# ui_codec.net
KiCad netlist of a schematic drawn in Altium Designer
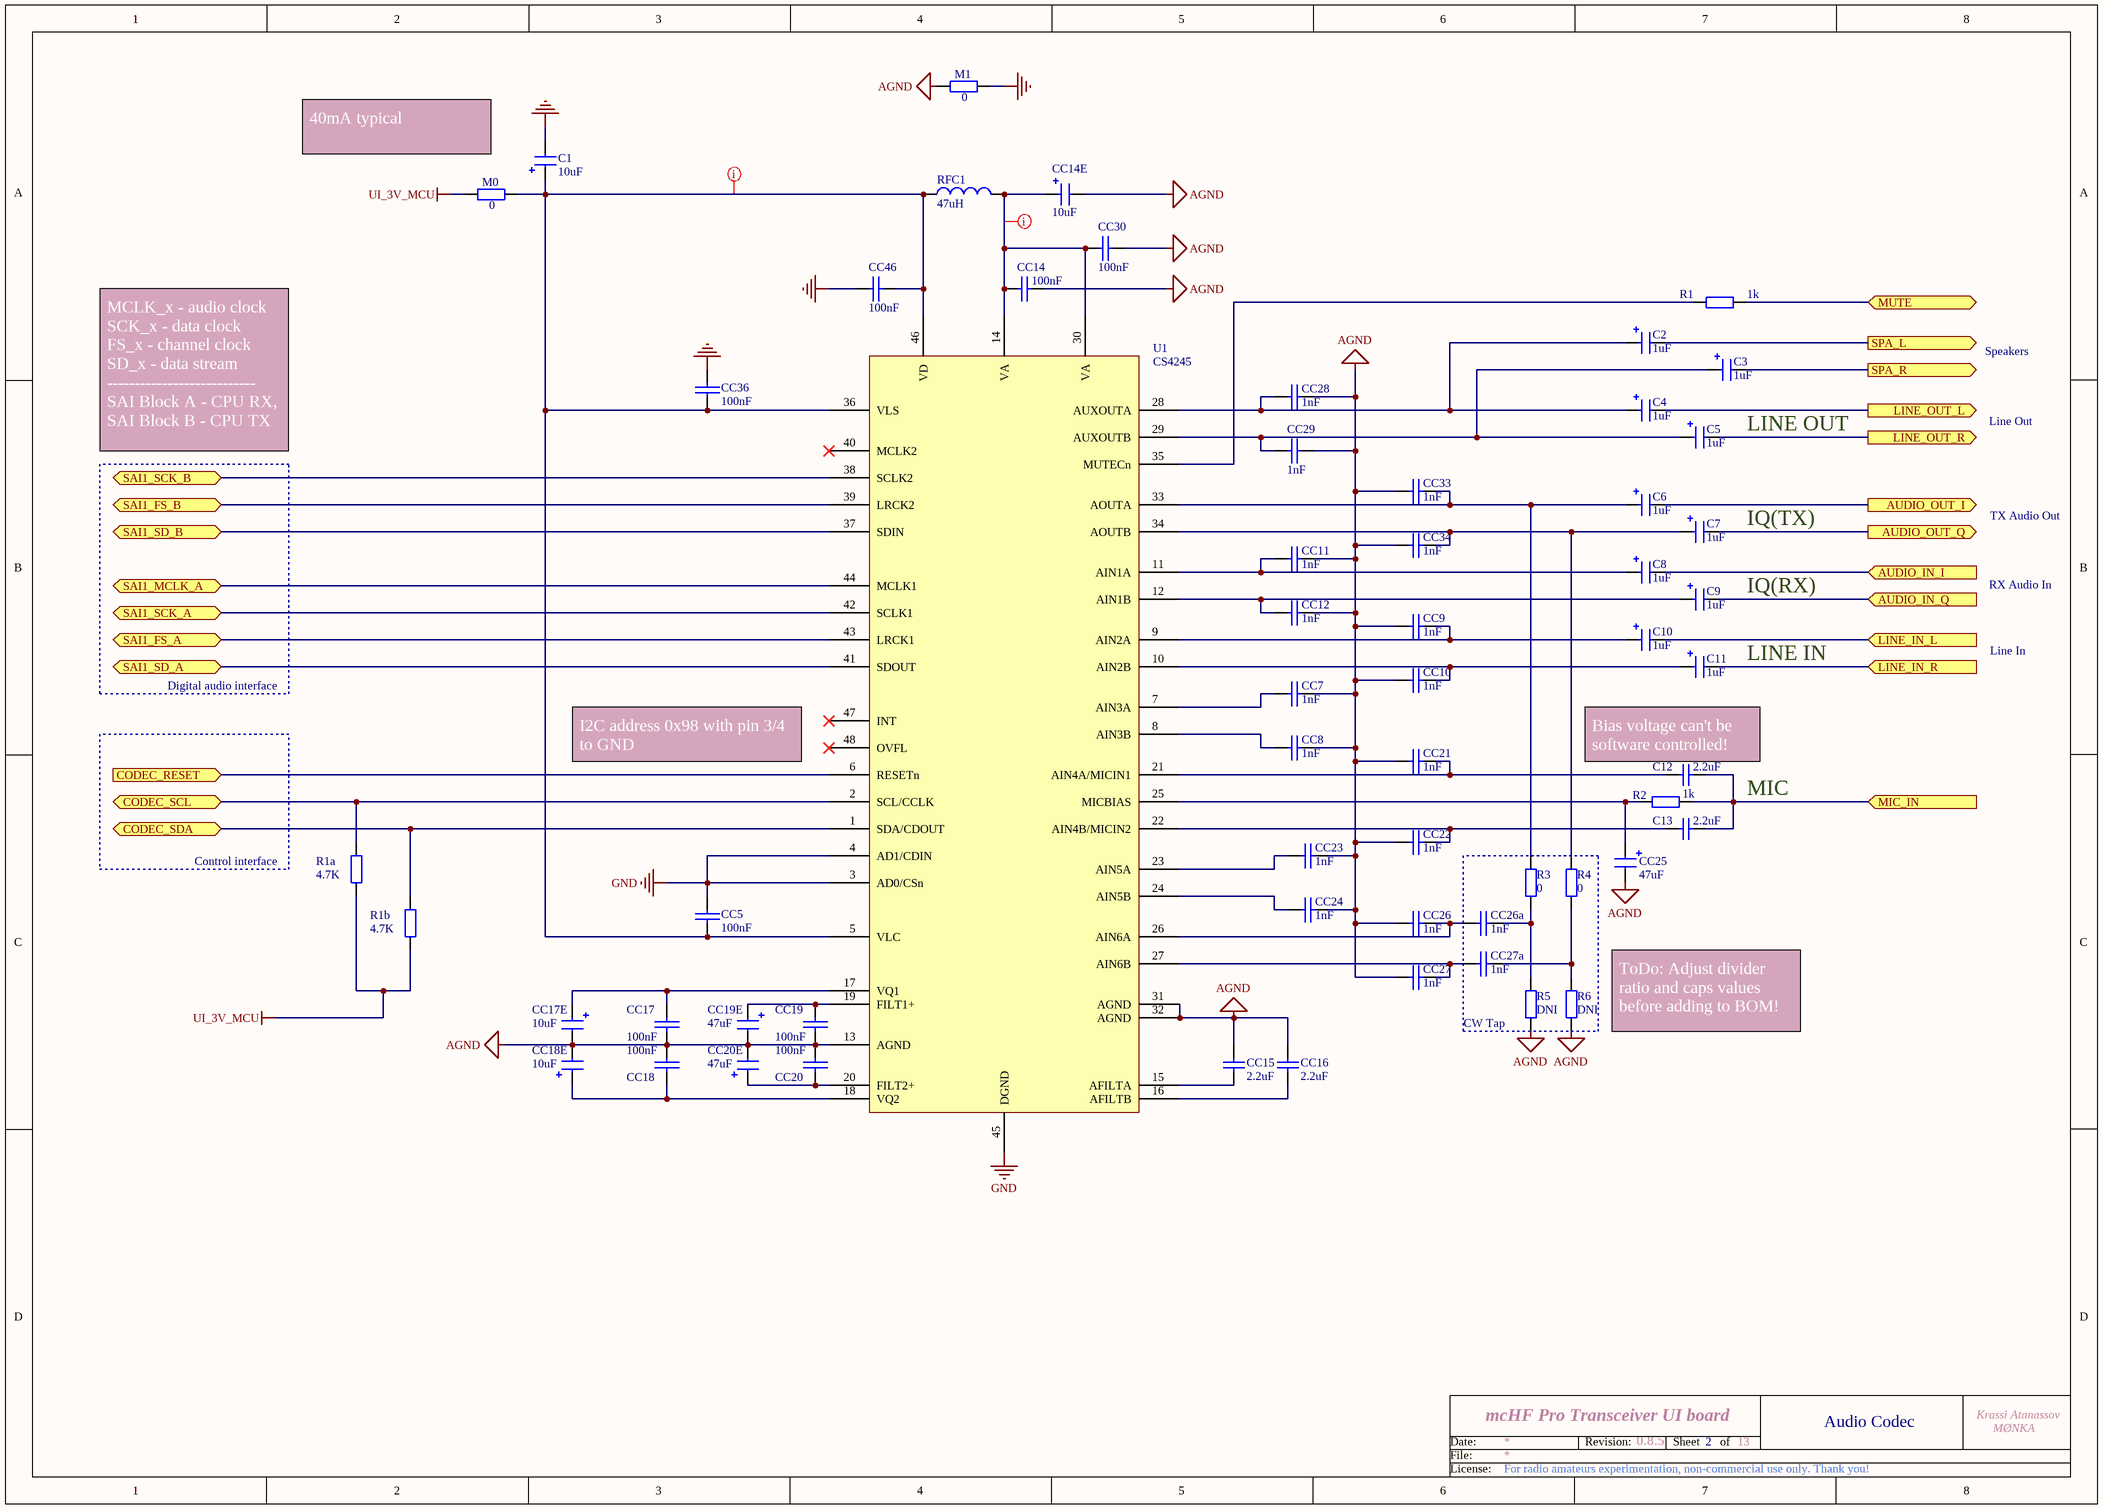
[diagram p0: ui_codec.SchDoc]

(export (version "E")
  (design (tool "Eeschema 10.0.6"))
  (components
    (comp (ref "C1")
      (value "10uF")
      (footprint "1206_Elec_Cap")
      (description "Electrolitic capacitor")
      (libsource (lib "mcHF_ui") (part "CAP-POL"))
    )
    (comp (ref "C2")
      (value "1uF")
      (footprint "1206_Elec_Cap")
      (description "Electrolitic capacitor")
      (libsource (lib "mcHF_ui") (part "CAP-POL"))
    )
    (comp (ref "C3")
      (value "1uF")
      (footprint "1206_Elec_Cap")
      (description "Electrolitic capacitor")
      (libsource (lib "mcHF_ui") (part "CAP-POL"))
    )
    (comp (ref "C4")
      (value "1uF")
      (footprint "1206_Elec_Cap")
      (description "Electrolitic capacitor")
      (libsource (lib "mcHF_ui") (part "CAP-POL"))
    )
    (comp (ref "C5")
      (value "1uF")
      (footprint "1206_Elec_Cap")
      (description "Electrolitic capacitor")
      (libsource (lib "mcHF_ui") (part "CAP-POL"))
    )
    (comp (ref "C6")
      (value "1uF")
      (footprint "1206_Elec_Cap")
      (description "Electrolitic capacitor")
      (libsource (lib "mcHF_ui") (part "CAP-POL"))
    )
    (comp (ref "C7")
      (value "1uF")
      (footprint "1206_Elec_Cap")
      (description "Electrolitic capacitor")
      (libsource (lib "mcHF_ui") (part "CAP-POL"))
    )
    (comp (ref "C8")
      (value "1uF")
      (footprint "1206_Elec_Cap")
      (description "Electrolitic capacitor")
      (libsource (lib "mcHF_ui") (part "CAP-POL"))
    )
    (comp (ref "C9")
      (value "1uF")
      (footprint "1206_Elec_Cap")
      (description "Electrolitic capacitor")
      (libsource (lib "mcHF_ui") (part "CAP-POL"))
    )
    (comp (ref "C10")
      (value "1uF")
      (footprint "1206_Elec_Cap")
      (description "Electrolitic capacitor")
      (libsource (lib "mcHF_ui") (part "CAP-POL"))
    )
    (comp (ref "C11")
      (value "1uF")
      (footprint "1206_Elec_Cap")
      (description "Electrolitic capacitor")
      (libsource (lib "mcHF_ui") (part "CAP-POL"))
    )
    (comp (ref "C12")
      (value "2.2uF")
      (footprint "0805")
      (description "Capacitor")
      (fields (field (name "PUBLISHER") "Altium Limited"))
      (libsource (lib "Miscellaneous Devices") (part "CAP"))
    )
    (comp (ref "C13")
      (value "2.2uF")
      (footprint "0805")
      (description "Capacitor")
      (fields (field (name "PUBLISHER") "Altium Limited"))
      (libsource (lib "Miscellaneous Devices") (part "CAP"))
    )
    (comp (ref "CC5")
      (value "100nF")
      (footprint "0805")
      (description "Capacitor")
      (libsource (lib "mcHF_ui") (part "CAP"))
    )
    (comp (ref "CC7")
      (value "1nF")
      (footprint "0805")
      (description "Capacitor")
      (libsource (lib "mcHF_ui") (part "CAP"))
    )
    (comp (ref "CC8")
      (value "1nF")
      (footprint "0805")
      (description "Capacitor")
      (libsource (lib "mcHF_ui") (part "CAP"))
    )
    (comp (ref "CC9")
      (value "1nF")
      (footprint "0805")
      (description "Capacitor")
      (libsource (lib "mcHF_ui") (part "CAP"))
    )
    (comp (ref "CC10")
      (value "1nF")
      (footprint "0805")
      (description "Capacitor")
      (libsource (lib "mcHF_ui") (part "CAP"))
    )
    (comp (ref "CC11")
      (value "1nF")
      (footprint "0805")
      (description "Capacitor")
      (libsource (lib "mcHF_ui") (part "CAP"))
    )
    (comp (ref "CC12")
      (value "1nF")
      (footprint "0805")
      (description "Capacitor")
      (libsource (lib "mcHF_ui") (part "CAP"))
    )
    (comp (ref "CC14")
      (value "100nF")
      (footprint "0805")
      (description "Capacitor")
      (libsource (lib "mcHF_ui") (part "CAP"))
    )
    (comp (ref "CC14E")
      (value "10uF")
      (footprint "1206_Elec_Cap")
      (description "Electrolitic capacitor")
      (libsource (lib "mcHF_ui") (part "CAP-POL"))
    )
    (comp (ref "CC15")
      (value "2.2uF")
      (footprint "0805")
      (description "Capacitor")
      (fields (field (name "PUBLISHER") "Altium Limited"))
      (libsource (lib "Miscellaneous Devices") (part "CAP"))
    )
    (comp (ref "CC16")
      (value "2.2uF")
      (footprint "0805")
      (description "Capacitor")
      (fields (field (name "PUBLISHER") "Altium Limited"))
      (libsource (lib "Miscellaneous Devices") (part "CAP"))
    )
    (comp (ref "CC17")
      (value "100nF")
      (footprint "0805")
      (description "Capacitor")
      (libsource (lib "mcHF_ui") (part "CAP"))
    )
    (comp (ref "CC17E")
      (value "10uF")
      (footprint "1206_Elec_Cap")
      (description "Electrolitic capacitor")
      (libsource (lib "mcHF_ui") (part "CAP-POL"))
    )
    (comp (ref "CC18")
      (value "100nF")
      (footprint "0805")
      (description "Capacitor")
      (libsource (lib "mcHF_ui") (part "CAP"))
    )
    (comp (ref "CC18E")
      (value "10uF")
      (footprint "1206_Elec_Cap")
      (description "Electrolitic capacitor")
      (libsource (lib "mcHF_ui") (part "CAP-POL"))
    )
    (comp (ref "CC19")
      (value "100nF")
      (footprint "0805")
      (description "Capacitor")
      (libsource (lib "mcHF_ui") (part "CAP"))
    )
    (comp (ref "CC19E")
      (value "47uF")
      (footprint "1206_Elec_Cap")
      (description "Electrolitic capacitor")
      (libsource (lib "mcHF_ui") (part "CAP-POL"))
    )
    (comp (ref "CC20")
      (value "100nF")
      (footprint "0805")
      (description "Capacitor")
      (libsource (lib "mcHF_ui") (part "CAP"))
    )
    (comp (ref "CC20E")
      (value "47uF")
      (footprint "1206_Elec_Cap")
      (description "Electrolitic capacitor")
      (libsource (lib "mcHF_ui") (part "CAP-POL"))
    )
    (comp (ref "CC21")
      (value "1nF")
      (footprint "0805")
      (description "Capacitor")
      (libsource (lib "mcHF_ui") (part "CAP"))
    )
    (comp (ref "CC22")
      (value "1nF")
      (footprint "0805")
      (description "Capacitor")
      (libsource (lib "mcHF_ui") (part "CAP"))
    )
    (comp (ref "CC23")
      (value "1nF")
      (footprint "0805")
      (description "Capacitor")
      (libsource (lib "mcHF_ui") (part "CAP"))
    )
    (comp (ref "CC24")
      (value "1nF")
      (footprint "0805")
      (description "Capacitor")
      (libsource (lib "mcHF_ui") (part "CAP"))
    )
    (comp (ref "CC25")
      (value "47uF")
      (footprint "1206_Elec_Cap")
      (description "Electrolitic capacitor")
      (libsource (lib "mcHF_ui") (part "CAP-POL"))
    )
    (comp (ref "CC26")
      (value "1nF")
      (footprint "0805")
      (description "Capacitor")
      (libsource (lib "mcHF_ui") (part "CAP"))
    )
    (comp (ref "CC26a")
      (value "1nF")
      (footprint "0805")
      (description "Capacitor")
      (libsource (lib "mcHF_ui") (part "CAP"))
    )
    (comp (ref "CC27")
      (value "1nF")
      (footprint "0805")
      (description "Capacitor")
      (libsource (lib "mcHF_ui") (part "CAP"))
    )
    (comp (ref "CC27a")
      (value "1nF")
      (footprint "0805")
      (description "Capacitor")
      (libsource (lib "mcHF_ui") (part "CAP"))
    )
    (comp (ref "CC28")
      (value "1nF")
      (footprint "0805")
      (description "Capacitor")
      (libsource (lib "mcHF_ui") (part "CAP"))
    )
    (comp (ref "CC29")
      (value "1nF")
      (footprint "0805")
      (description "Capacitor")
      (libsource (lib "mcHF_ui") (part "CAP"))
    )
    (comp (ref "CC30")
      (value "100nF")
      (footprint "0805")
      (description "Capacitor")
      (libsource (lib "mcHF_ui") (part "CAP"))
    )
    (comp (ref "CC33")
      (value "1nF")
      (footprint "0805")
      (description "Capacitor")
      (libsource (lib "mcHF_ui") (part "CAP"))
    )
    (comp (ref "CC34")
      (value "1nF")
      (footprint "0805")
      (description "Capacitor")
      (libsource (lib "mcHF_ui") (part "CAP"))
    )
    (comp (ref "CC36")
      (value "100nF")
      (footprint "0805")
      (description "Capacitor")
      (libsource (lib "mcHF_ui") (part "CAP"))
    )
    (comp (ref "CC46")
      (value "100nF")
      (footprint "0805")
      (description "Capacitor")
      (libsource (lib "mcHF_ui") (part "CAP"))
    )
    (comp (ref "M0")
      (value "0")
      (footprint "0805")
      (description "Resistor")
      (libsource (lib "mcHF_rf") (part "RES"))
    )
    (comp (ref "M1")
      (value "0")
      (footprint "0805")
      (description "Resistor")
      (libsource (lib "mcHF_rf") (part "RES"))
    )
    (comp (ref "R1")
      (value "1k")
      (footprint "0805")
      (description "Resistor")
      (libsource (lib "") (part "RES_1"))
    )
    (comp (ref "R1a")
      (value "4.7K")
      (footprint "0805")
      (description "Resistor")
      (libsource (lib "*") (part "RES"))
    )
    (comp (ref "R1b")
      (value "4.7K")
      (footprint "0805")
      (description "Resistor")
      (libsource (lib "*") (part "RES"))
    )
    (comp (ref "R2")
      (value "1k")
      (footprint "0805")
      (description "Resistor")
      (libsource (lib "") (part "RES_1"))
    )
    (comp (ref "R3")
      (value "0")
      (footprint "0805")
      (description "Resistor")
      (libsource (lib "mcHF_ui") (part "RES"))
    )
    (comp (ref "R4")
      (value "0")
      (footprint "0805")
      (description "Resistor")
      (libsource (lib "mcHF_ui") (part "RES"))
    )
    (comp (ref "R5")
      (value "DNI")
      (footprint "0805")
      (description "Resistor")
      (libsource (lib "mcHF_ui") (part "RES"))
    )
    (comp (ref "R6")
      (value "DNI")
      (footprint "0805")
      (description "Resistor")
      (libsource (lib "mcHF_ui") (part "RES"))
    )
    (comp (ref "RFC1")
      (value "47uH")
      (footprint "0805")
      (description "Inductor")
      (libsource (lib "mcHF_ui") (part "Inductor"))
    )
    (comp (ref "U1")
      (value "CS4245")
      (footprint "QUAD48")
      (description "Audio CODEC")
      (libsource (lib "__ui") (part "CS4245"))
    )
  )
  (nets
    (net (code "1") (name "/AUDIO_IN_I") (class "Default")
      (node (ref "C8") (pin "2") (pinfunction "2_2") (pintype "passive"))
    )
    (net (code "2") (name "/AUDIO_IN_Q") (class "Default")
      (node (ref "C9") (pin "2") (pinfunction "2_2") (pintype "passive"))
    )
    (net (code "3") (name "/AUDIO_OUT_I") (class "Default")
      (node (ref "C6") (pin "2") (pinfunction "2_2") (pintype "passive"))
    )
    (net (code "4") (name "/AUDIO_OUT_Q") (class "Default")
      (node (ref "C7") (pin "2") (pinfunction "2_2") (pintype "passive"))
    )
    (net (code "5") (name "/CODEC_RESET") (class "Default")
      (node (ref "U1") (pin "6") (pinfunction "RESETn_6") (pintype "passive"))
    )
    (net (code "6") (name "/CODEC_SCL") (class "Default")
      (node (ref "R1a") (pin "1") (pinfunction "1_1") (pintype "passive"))
      (node (ref "U1") (pin "2") (pinfunction "SCL/CCLK_2") (pintype "passive"))
    )
    (net (code "7") (name "/CODEC_SDA") (class "Default")
      (node (ref "R1b") (pin "1") (pinfunction "1_1") (pintype "passive"))
      (node (ref "U1") (pin "1") (pinfunction "SDA/CDOUT_1") (pintype "passive"))
    )
    (net (code "8") (name "/LINE_IN_L") (class "Default")
      (node (ref "C10") (pin "2") (pinfunction "2_2") (pintype "passive"))
    )
    (net (code "9") (name "/LINE_IN_R") (class "Default")
      (node (ref "C11") (pin "2") (pinfunction "2_2") (pintype "passive"))
    )
    (net (code "10") (name "/LINE_OUT_L") (class "Default")
      (node (ref "C4") (pin "2") (pinfunction "2_2") (pintype "passive"))
    )
    (net (code "11") (name "/LINE_OUT_R") (class "Default")
      (node (ref "C5") (pin "2") (pinfunction "2_2") (pintype "passive"))
    )
    (net (code "12") (name "/MIC_IN") (class "Default")
      (node (ref "C12") (pin "2") (pinfunction "2_2") (pintype "passive"))
      (node (ref "C13") (pin "2") (pinfunction "2_2") (pintype "passive"))
      (node (ref "R2") (pin "1") (pinfunction "1_1") (pintype "passive"))
    )
    (net (code "13") (name "/MUTE") (class "Default")
      (node (ref "R1") (pin "1") (pinfunction "1_1") (pintype "passive"))
    )
    (net (code "14") (name "/SAI1_FS_A") (class "Default")
      (node (ref "U1") (pin "43") (pinfunction "LRCK1_43") (pintype "passive"))
    )
    (net (code "15") (name "/SAI1_FS_B") (class "Default")
      (node (ref "U1") (pin "39") (pinfunction "LRCK2_39") (pintype "passive"))
    )
    (net (code "16") (name "/SAI1_MCLK_A") (class "Default")
      (node (ref "U1") (pin "44") (pinfunction "MCLK1_44") (pintype "passive"))
    )
    (net (code "17") (name "/SAI1_SCK_A") (class "Default")
      (node (ref "U1") (pin "42") (pinfunction "SCLK1_42") (pintype "passive"))
    )
    (net (code "18") (name "/SAI1_SCK_B") (class "Default")
      (node (ref "U1") (pin "38") (pinfunction "SCLK2_38") (pintype "passive"))
    )
    (net (code "19") (name "/SAI1_SD_A") (class "Default")
      (node (ref "U1") (pin "41") (pinfunction "SDOUT_41") (pintype "passive"))
    )
    (net (code "20") (name "/SAI1_SD_B") (class "Default")
      (node (ref "U1") (pin "37") (pinfunction "SDIN_37") (pintype "passive"))
    )
    (net (code "21") (name "/SPA_L") (class "Default")
      (node (ref "C2") (pin "2") (pinfunction "2_2") (pintype "passive"))
    )
    (net (code "22") (name "/SPA_R") (class "Default")
      (node (ref "C3") (pin "2") (pinfunction "2_2") (pintype "passive"))
    )
    (net (code "23") (name "AGND") (class "Default")
      (node (ref "CC10") (pin "2") (pinfunction "2_2") (pintype "passive"))
      (node (ref "CC11") (pin "1") (pinfunction "1_1") (pintype "passive"))
      (node (ref "CC12") (pin "1") (pinfunction "1_1") (pintype "passive"))
      (node (ref "CC14") (pin "1") (pinfunction "1_1") (pintype "passive"))
      (node (ref "CC14E") (pin "2") (pinfunction "2_2") (pintype "passive"))
      (node (ref "CC15") (pin "1") (pinfunction "1_1") (pintype "passive"))
      (node (ref "CC16") (pin "1") (pinfunction "1_1") (pintype "passive"))
      (node (ref "CC17") (pin "1") (pinfunction "1_1") (pintype "passive"))
      (node (ref "CC17E") (pin "2") (pinfunction "2_2") (pintype "passive"))
      (node (ref "CC18") (pin "2") (pinfunction "2_2") (pintype "passive"))
      (node (ref "CC18E") (pin "2") (pinfunction "2_2") (pintype "passive"))
      (node (ref "CC19") (pin "1") (pinfunction "1_1") (pintype "passive"))
      (node (ref "CC19E") (pin "2") (pinfunction "2_2") (pintype "passive"))
      (node (ref "CC20") (pin "2") (pinfunction "2_2") (pintype "passive"))
      (node (ref "CC20E") (pin "2") (pinfunction "2_2") (pintype "passive"))
      (node (ref "CC21") (pin "2") (pinfunction "2_2") (pintype "passive"))
      (node (ref "CC22") (pin "2") (pinfunction "2_2") (pintype "passive"))
      (node (ref "CC23") (pin "1") (pinfunction "1_1") (pintype "passive"))
      (node (ref "CC24") (pin "1") (pinfunction "1_1") (pintype "passive"))
      (node (ref "CC25") (pin "2") (pinfunction "2_2") (pintype "passive"))
      (node (ref "CC26") (pin "2") (pinfunction "2_2") (pintype "passive"))
      (node (ref "CC27") (pin "2") (pinfunction "2_2") (pintype "passive"))
      (node (ref "CC28") (pin "1") (pinfunction "1_1") (pintype "passive"))
      (node (ref "CC29") (pin "1") (pinfunction "1_1") (pintype "passive"))
      (node (ref "CC30") (pin "1") (pinfunction "1_1") (pintype "passive"))
      (node (ref "CC33") (pin "2") (pinfunction "2_2") (pintype "passive"))
      (node (ref "CC34") (pin "2") (pinfunction "2_2") (pintype "passive"))
      (node (ref "CC7") (pin "1") (pinfunction "1_1") (pintype "passive"))
      (node (ref "CC8") (pin "1") (pinfunction "1_1") (pintype "passive"))
      (node (ref "CC9") (pin "2") (pinfunction "2_2") (pintype "passive"))
      (node (ref "M1") (pin "2") (pinfunction "2_2") (pintype "passive"))
      (node (ref "R5") (pin "2") (pinfunction "2_2") (pintype "passive"))
      (node (ref "R6") (pin "2") (pinfunction "2_2") (pintype "passive"))
      (node (ref "U1") (pin "13") (pinfunction "AGND_13") (pintype "passive"))
      (node (ref "U1") (pin "31") (pinfunction "AGND_31") (pintype "passive"))
      (node (ref "U1") (pin "32") (pinfunction "AGND_32") (pintype "passive"))
    )
    (net (code "24") (name "GND") (class "Default")
      (node (ref "C1") (pin "2") (pinfunction "2_2") (pintype "passive"))
      (node (ref "CC36") (pin "2") (pinfunction "2_2") (pintype "passive"))
      (node (ref "CC46") (pin "2") (pinfunction "2_2") (pintype "passive"))
      (node (ref "CC5") (pin "2") (pinfunction "2_2") (pintype "passive"))
      (node (ref "M1") (pin "1") (pinfunction "1_1") (pintype "passive"))
      (node (ref "U1") (pin "3") (pinfunction "AD0/CSn_3") (pintype "passive"))
      (node (ref "U1") (pin "4") (pinfunction "AD1/CDIN_4") (pintype "passive"))
      (node (ref "U1") (pin "45") (pinfunction "DGND_45") (pintype "passive"))
    )
    (net (code "25") (name "Net-(CC14-Pad2)") (class "Default")
      (node (ref "CC14") (pin "2") (pinfunction "2_2") (pintype "passive"))
      (node (ref "CC14E") (pin "1") (pinfunction "1_1") (pintype "passive"))
      (node (ref "CC30") (pin "2") (pinfunction "2_2") (pintype "passive"))
      (node (ref "RFC1") (pin "2") (pinfunction "2_2") (pintype "passive"))
      (node (ref "U1") (pin "14") (pinfunction "VA_14") (pintype "passive"))
      (node (ref "U1") (pin "30") (pinfunction "VA_30") (pintype "passive"))
    )
    (net (code "26") (name "Net-(CC26a-Pad1)") (class "Default")
      (node (ref "CC26a") (pin "1") (pinfunction "1_1") (pintype "passive"))
      (node (ref "R3") (pin "2") (pinfunction "2_2") (pintype "passive"))
      (node (ref "R5") (pin "1") (pinfunction "1_1") (pintype "passive"))
    )
    (net (code "27") (name "Net-(CC27a-Pad1)") (class "Default")
      (node (ref "CC27a") (pin "1") (pinfunction "1_1") (pintype "passive"))
      (node (ref "R4") (pin "2") (pinfunction "2_2") (pintype "passive"))
      (node (ref "R6") (pin "1") (pinfunction "1_1") (pintype "passive"))
    )
    (net (code "28") (name "Net-(U1-AFILTA)") (class "Default")
      (node (ref "CC15") (pin "2") (pinfunction "2_2") (pintype "passive"))
      (node (ref "U1") (pin "15") (pinfunction "AFILTA_15") (pintype "passive"))
    )
    (net (code "29") (name "Net-(U1-AFILTB)") (class "Default")
      (node (ref "CC16") (pin "2") (pinfunction "2_2") (pintype "passive"))
      (node (ref "U1") (pin "16") (pinfunction "AFILTB_16") (pintype "passive"))
    )
    (net (code "30") (name "Net-(U1-AIN1A)") (class "Default")
      (node (ref "C8") (pin "1") (pinfunction "1_1") (pintype "passive"))
      (node (ref "CC11") (pin "2") (pinfunction "2_2") (pintype "passive"))
      (node (ref "U1") (pin "11") (pinfunction "AIN1A_11") (pintype "passive"))
    )
    (net (code "31") (name "Net-(U1-AIN1B)") (class "Default")
      (node (ref "C9") (pin "1") (pinfunction "1_1") (pintype "passive"))
      (node (ref "CC12") (pin "2") (pinfunction "2_2") (pintype "passive"))
      (node (ref "U1") (pin "12") (pinfunction "AIN1B_12") (pintype "passive"))
    )
    (net (code "32") (name "Net-(U1-AIN2A)") (class "Default")
      (node (ref "C10") (pin "1") (pinfunction "1_1") (pintype "passive"))
      (node (ref "CC9") (pin "1") (pinfunction "1_1") (pintype "passive"))
      (node (ref "U1") (pin "9") (pinfunction "AIN2A_9") (pintype "passive"))
    )
    (net (code "33") (name "Net-(U1-AIN2B)") (class "Default")
      (node (ref "C11") (pin "1") (pinfunction "1_1") (pintype "passive"))
      (node (ref "CC10") (pin "1") (pinfunction "1_1") (pintype "passive"))
      (node (ref "U1") (pin "10") (pinfunction "AIN2B_10") (pintype "passive"))
    )
    (net (code "34") (name "Net-(U1-AIN3A)") (class "Default")
      (node (ref "CC7") (pin "2") (pinfunction "2_2") (pintype "passive"))
      (node (ref "U1") (pin "7") (pinfunction "AIN3A_7") (pintype "passive"))
    )
    (net (code "35") (name "Net-(U1-AIN3B)") (class "Default")
      (node (ref "CC8") (pin "2") (pinfunction "2_2") (pintype "passive"))
      (node (ref "U1") (pin "8") (pinfunction "AIN3B_8") (pintype "passive"))
    )
    (net (code "36") (name "Net-(U1-AIN4A{slash}MICIN1)") (class "Default")
      (node (ref "C12") (pin "1") (pinfunction "1_1") (pintype "passive"))
      (node (ref "CC21") (pin "1") (pinfunction "1_1") (pintype "passive"))
      (node (ref "U1") (pin "21") (pinfunction "AIN4A/MICIN1_21") (pintype "passive"))
    )
    (net (code "37") (name "Net-(U1-AIN4B{slash}MICIN2)") (class "Default")
      (node (ref "C13") (pin "1") (pinfunction "1_1") (pintype "passive"))
      (node (ref "CC22") (pin "1") (pinfunction "1_1") (pintype "passive"))
      (node (ref "U1") (pin "22") (pinfunction "AIN4B/MICIN2_22") (pintype "passive"))
    )
    (net (code "38") (name "Net-(U1-AIN5A)") (class "Default")
      (node (ref "CC23") (pin "2") (pinfunction "2_2") (pintype "passive"))
      (node (ref "U1") (pin "23") (pinfunction "AIN5A_23") (pintype "passive"))
    )
    (net (code "39") (name "Net-(U1-AIN5B)") (class "Default")
      (node (ref "CC24") (pin "2") (pinfunction "2_2") (pintype "passive"))
      (node (ref "U1") (pin "24") (pinfunction "AIN5B_24") (pintype "passive"))
    )
    (net (code "40") (name "Net-(U1-AIN6A)") (class "Default")
      (node (ref "CC26") (pin "1") (pinfunction "1_1") (pintype "passive"))
      (node (ref "CC26a") (pin "2") (pinfunction "2_2") (pintype "passive"))
      (node (ref "U1") (pin "26") (pinfunction "AIN6A_26") (pintype "passive"))
    )
    (net (code "41") (name "Net-(U1-AIN6B)") (class "Default")
      (node (ref "CC27") (pin "1") (pinfunction "1_1") (pintype "passive"))
      (node (ref "CC27a") (pin "2") (pinfunction "2_2") (pintype "passive"))
      (node (ref "U1") (pin "27") (pinfunction "AIN6B_27") (pintype "passive"))
    )
    (net (code "42") (name "Net-(U1-AOUTA)") (class "Default")
      (node (ref "C6") (pin "1") (pinfunction "1_1") (pintype "passive"))
      (node (ref "CC33") (pin "1") (pinfunction "1_1") (pintype "passive"))
      (node (ref "R3") (pin "1") (pinfunction "1_1") (pintype "passive"))
      (node (ref "U1") (pin "33") (pinfunction "AOUTA_33") (pintype "passive"))
    )
    (net (code "43") (name "Net-(U1-AOUTB)") (class "Default")
      (node (ref "C7") (pin "1") (pinfunction "1_1") (pintype "passive"))
      (node (ref "CC34") (pin "1") (pinfunction "1_1") (pintype "passive"))
      (node (ref "R4") (pin "1") (pinfunction "1_1") (pintype "passive"))
      (node (ref "U1") (pin "34") (pinfunction "AOUTB_34") (pintype "passive"))
    )
    (net (code "44") (name "Net-(U1-AUXOUTA)") (class "Default")
      (node (ref "C2") (pin "1") (pinfunction "1_1") (pintype "passive"))
      (node (ref "C4") (pin "1") (pinfunction "1_1") (pintype "passive"))
      (node (ref "CC28") (pin "2") (pinfunction "2_2") (pintype "passive"))
      (node (ref "U1") (pin "28") (pinfunction "AUXOUTA_28") (pintype "passive"))
    )
    (net (code "45") (name "Net-(U1-AUXOUTB)") (class "Default")
      (node (ref "C3") (pin "1") (pinfunction "1_1") (pintype "passive"))
      (node (ref "C5") (pin "1") (pinfunction "1_1") (pintype "passive"))
      (node (ref "CC29") (pin "2") (pinfunction "2_2") (pintype "passive"))
      (node (ref "U1") (pin "29") (pinfunction "AUXOUTB_29") (pintype "passive"))
    )
    (net (code "46") (name "Net-(U1-FILT1+)") (class "Default")
      (node (ref "CC19") (pin "2") (pinfunction "2_2") (pintype "passive"))
      (node (ref "CC19E") (pin "1") (pinfunction "1_1") (pintype "passive"))
      (node (ref "U1") (pin "19") (pinfunction "FILT1+_19") (pintype "passive"))
    )
    (net (code "47") (name "Net-(U1-FILT2+)") (class "Default")
      (node (ref "CC20") (pin "1") (pinfunction "1_1") (pintype "passive"))
      (node (ref "CC20E") (pin "1") (pinfunction "1_1") (pintype "passive"))
      (node (ref "U1") (pin "20") (pinfunction "FILT2+_20") (pintype "passive"))
    )
    (net (code "48") (name "Net-(U1-MICBIAS)") (class "Default")
      (node (ref "CC25") (pin "1") (pinfunction "1_1") (pintype "passive"))
      (node (ref "R2") (pin "2") (pinfunction "2_2") (pintype "passive"))
      (node (ref "U1") (pin "25") (pinfunction "MICBIAS_25") (pintype "passive"))
    )
    (net (code "49") (name "Net-(U1-MUTECn)") (class "Default")
      (node (ref "R1") (pin "2") (pinfunction "2_2") (pintype "passive"))
      (node (ref "U1") (pin "35") (pinfunction "MUTECn_35") (pintype "passive"))
    )
    (net (code "50") (name "Net-(U1-VD)") (class "Default")
      (node (ref "C1") (pin "1") (pinfunction "1_1") (pintype "passive"))
      (node (ref "CC36") (pin "1") (pinfunction "1_1") (pintype "passive"))
      (node (ref "CC46") (pin "1") (pinfunction "1_1") (pintype "passive"))
      (node (ref "CC5") (pin "1") (pinfunction "1_1") (pintype "passive"))
      (node (ref "M0") (pin "1") (pinfunction "1_1") (pintype "passive"))
      (node (ref "RFC1") (pin "1") (pinfunction "1_1") (pintype "passive"))
      (node (ref "U1") (pin "36") (pinfunction "VLS_36") (pintype "passive"))
      (node (ref "U1") (pin "46") (pinfunction "VD_46") (pintype "passive"))
      (node (ref "U1") (pin "5") (pinfunction "VLC_5") (pintype "passive"))
    )
    (net (code "51") (name "Net-(U1-VQ1)") (class "Default")
      (node (ref "CC17") (pin "2") (pinfunction "2_2") (pintype "passive"))
      (node (ref "CC17E") (pin "1") (pinfunction "1_1") (pintype "passive"))
      (node (ref "U1") (pin "17") (pinfunction "VQ1_17") (pintype "passive"))
    )
    (net (code "52") (name "Net-(U1-VQ2)") (class "Default")
      (node (ref "CC18") (pin "1") (pinfunction "1_1") (pintype "passive"))
      (node (ref "CC18E") (pin "1") (pinfunction "1_1") (pintype "passive"))
      (node (ref "U1") (pin "18") (pinfunction "VQ2_18") (pintype "passive"))
    )
    (net (code "53") (name "UI_3V_MCU") (class "Default")
      (node (ref "M0") (pin "2") (pinfunction "2_2") (pintype "passive"))
      (node (ref "R1a") (pin "2") (pinfunction "2_2") (pintype "passive"))
      (node (ref "R1b") (pin "2") (pinfunction "2_2") (pintype "passive"))
    )
    (net (code "54") (name "unconnected-(U1-INT-Pad47)") (class "Default")
      (node (ref "U1") (pin "47") (pinfunction "INT_47") (pintype "passive+no_connect"))
    )
    (net (code "55") (name "unconnected-(U1-MCLK2-Pad40)") (class "Default")
      (node (ref "U1") (pin "40") (pinfunction "MCLK2_40") (pintype "passive+no_connect"))
    )
    (net (code "56") (name "unconnected-(U1-OVFL-Pad48)") (class "Default")
      (node (ref "U1") (pin "48") (pinfunction "OVFL_48") (pintype "passive+no_connect"))
    )
  )
)
